# eth_part.net
KiCad netlist of a schematic drawn in Altium Designer
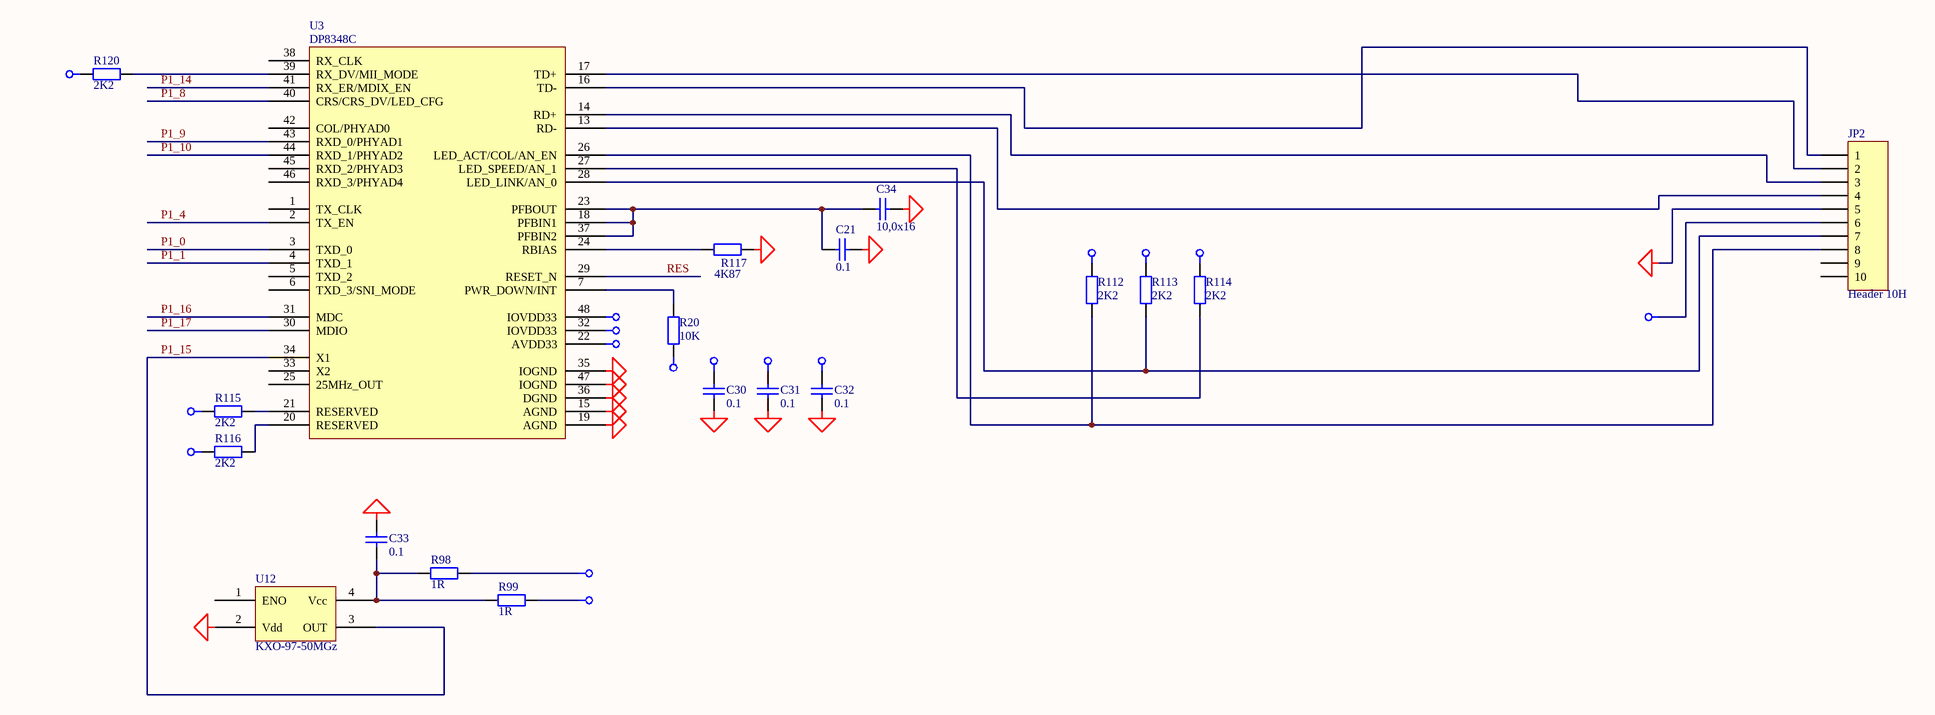
[diagram p0: eth_part.SchDoc]

(export (version "E")
  (design (tool "Eeschema 10.0.6"))
  (components
    (comp (ref "C21")
      (value "0.1")
      (footprint "C3216-1206")
      (description "Capacitor (Semiconductor SIM Model)")
      (fields (field (name "MANUFACTURER") "Generic Components") (field (name "PUBLISHER") "Altium Limited"))
      (libsource (lib "Miscellaneous Devices") (part "Cap Semi"))
    )
    (comp (ref "C30")
      (value "0.1")
      (footprint "_1206")
      (description "Capacitor (Semiconductor SIM Model)")
      (fields (field (name "MANUFACTURER") "Generic Components") (field (name "PUBLISHER") "Altium Limited"))
      (libsource (lib "Miscellaneous Devices") (part "Cap Semi"))
    )
    (comp (ref "C31")
      (value "0.1")
      (footprint "_1206")
      (description "Capacitor (Semiconductor SIM Model)")
      (fields (field (name "MANUFACTURER") "Generic Components") (field (name "PUBLISHER") "Altium Limited"))
      (libsource (lib "Miscellaneous Devices") (part "Cap Semi"))
    )
    (comp (ref "C32")
      (value "0.1")
      (footprint "_1206")
      (description "Capacitor (Semiconductor SIM Model)")
      (fields (field (name "MANUFACTURER") "Generic Components") (field (name "PUBLISHER") "Altium Limited"))
      (libsource (lib "Miscellaneous Devices") (part "Cap Semi"))
    )
    (comp (ref "C33")
      (value "0.1")
      (footprint "_1206")
      (description "Capacitor (Semiconductor SIM Model)")
      (fields (field (name "MANUFACTURER") "Generic Components") (field (name "PUBLISHER") "Altium Limited"))
      (libsource (lib "Miscellaneous Devices") (part "Cap Semi"))
    )
    (comp (ref "C34")
      (value "10,0x16")
      (footprint "C3216-1206")
      (description "Capacitor (Semiconductor SIM Model)")
      (fields (field (name "MANUFACTURER") "Generic Components") (field (name "PUBLISHER") "Altium Limited"))
      (libsource (lib "Miscellaneous Devices") (part "Cap Semi"))
    )
    (comp (ref "JP2")
      (value "Header 10H")
      (footprint "HDR2X5")
      (description "Header, 10-Pin, Right Angle")
      (fields (field (name "MANUFACTURER") "Generic Components") (field (name "PUBLISHER") "Altium Limited"))
      (libsource (lib "Miscellaneous Connectors") (part "Header 10H"))
    )
    (comp (ref "R20")
      (value "10K")
      (footprint "_1206")
      (description "Resistor")
      (fields (field (name "MANUFACTURER") "Generic Components") (field (name "PUBLISHER") "Altium Limited"))
      (libsource (lib "") (part "Res2_3"))
    )
    (comp (ref "R98")
      (value "1R")
      (footprint "_1206")
      (description "Resistor")
      (fields (field (name "MANUFACTURER") "Generic Components") (field (name "PUBLISHER") "Altium Limited"))
      (libsource (lib "") (part "Res2_1"))
    )
    (comp (ref "R99")
      (value "1R")
      (footprint "_1206")
      (description "Resistor")
      (fields (field (name "MANUFACTURER") "Generic Components") (field (name "PUBLISHER") "Altium Limited"))
      (libsource (lib "") (part "Res2_1"))
    )
    (comp (ref "R112")
      (value "2K2")
      (footprint "_1206")
      (description "Resistor")
      (fields (field (name "MANUFACTURER") "Generic Components") (field (name "PUBLISHER") "Altium Limited"))
      (libsource (lib "") (part "Res2_2"))
    )
    (comp (ref "R113")
      (value "2K2")
      (footprint "_1206")
      (description "Resistor")
      (fields (field (name "MANUFACTURER") "Generic Components") (field (name "PUBLISHER") "Altium Limited"))
      (libsource (lib "") (part "Res2_2"))
    )
    (comp (ref "R114")
      (value "2K2")
      (footprint "_1206")
      (description "Resistor")
      (fields (field (name "MANUFACTURER") "Generic Components") (field (name "PUBLISHER") "Altium Limited"))
      (libsource (lib "") (part "Res2_2"))
    )
    (comp (ref "R115")
      (value "2K2")
      (footprint "_1206")
      (description "Resistor")
      (fields (field (name "MANUFACTURER") "Generic Components") (field (name "PUBLISHER") "Altium Limited"))
      (libsource (lib "Miscellaneous Devices") (part "Res2"))
    )
    (comp (ref "R116")
      (value "2K2")
      (footprint "_1206")
      (description "Resistor")
      (fields (field (name "MANUFACTURER") "Generic Components") (field (name "PUBLISHER") "Altium Limited"))
      (libsource (lib "Miscellaneous Devices") (part "Res2"))
    )
    (comp (ref "R117")
      (value "4K87")
      (footprint "_1206")
      (description "Resistor")
      (fields (field (name "MANUFACTURER") "Generic Components") (field (name "PUBLISHER") "Altium Limited"))
      (libsource (lib "Miscellaneous Devices") (part "Res2"))
    )
    (comp (ref "R120")
      (value "2K2")
      (footprint "_1206")
      (description "Resistor")
      (fields (field (name "MANUFACTURER") "Generic Components") (field (name "PUBLISHER") "Altium Limited"))
      (libsource (lib "Miscellaneous Devices") (part "Res2"))
    )
    (comp (ref "U3") (value "DP8348C") (footprint "F-QFP7X7-G48/N") (libsource (lib "PAL") (part "DP8348C")))
    (comp (ref "U12") (value "KXO-97-50MGz") (footprint "KXO-97") (libsource (lib "PAL") (part "KXO-97")))
  )
  (nets
    (net (code "1") (name "+3v3") (class "Default")
      (node (ref "C30") (pin "1") (pinfunction "1_1") (pintype "passive"))
      (node (ref "C31") (pin "1") (pinfunction "1_1") (pintype "passive"))
      (node (ref "C32") (pin "1") (pinfunction "1_1") (pintype "passive"))
      (node (ref "JP2") (pin "6") (pinfunction "6_6") (pintype "passive"))
      (node (ref "R112") (pin "2") (pinfunction "2_2") (pintype "passive"))
      (node (ref "R113") (pin "2") (pinfunction "2_2") (pintype "passive"))
      (node (ref "R114") (pin "2") (pinfunction "2_2") (pintype "passive"))
      (node (ref "R115") (pin "2") (pinfunction "2_2") (pintype "passive"))
      (node (ref "R116") (pin "2") (pinfunction "2_2") (pintype "passive"))
      (node (ref "R120") (pin "2") (pinfunction "2_2") (pintype "passive"))
      (node (ref "R20") (pin "2") (pinfunction "2_2") (pintype "passive"))
      (node (ref "R99") (pin "2") (pinfunction "2_2") (pintype "passive"))
      (node (ref "U3") (pin "22") (pinfunction "AVDD33_22") (pintype "passive"))
      (node (ref "U3") (pin "32") (pinfunction "IOVDD33_32") (pintype "passive"))
      (node (ref "U3") (pin "48") (pinfunction "IOVDD33_48") (pintype "passive"))
    )
    (net (code "2") (name "+5v") (class "Default")
      (node (ref "R98") (pin "2") (pinfunction "2_2") (pintype "passive"))
    )
    (net (code "3") (name "/P1_0") (class "Default")
      (node (ref "U3") (pin "3") (pinfunction "TXD_0_3") (pintype "passive"))
    )
    (net (code "4") (name "/P1_1") (class "Default")
      (node (ref "U3") (pin "4") (pinfunction "TXD_1_4") (pintype "passive"))
    )
    (net (code "5") (name "/P1_4") (class "Default")
      (node (ref "U3") (pin "2") (pinfunction "TX_EN_2") (pintype "passive"))
    )
    (net (code "6") (name "/P1_8") (class "Default")
      (node (ref "U3") (pin "40") (pinfunction "CRS/CRS_DV/LED_CFG_40") (pintype "passive"))
    )
    (net (code "7") (name "/P1_9") (class "Default")
      (node (ref "U3") (pin "43") (pinfunction "RXD_0/PHYAD1_43") (pintype "passive"))
    )
    (net (code "8") (name "/P1_10") (class "Default")
      (node (ref "U3") (pin "44") (pinfunction "RXD_1/PHYAD2_44") (pintype "passive"))
    )
    (net (code "9") (name "/P1_14") (class "Default")
      (node (ref "U3") (pin "41") (pinfunction "RX_ER/MDIX_EN_41") (pintype "passive"))
    )
    (net (code "10") (name "/P1_15") (class "Default")
      (node (ref "U12") (pin "3") (pinfunction "OUT_3") (pintype "passive"))
      (node (ref "U3") (pin "34") (pinfunction "X1_34") (pintype "passive"))
    )
    (net (code "11") (name "/P1_16") (class "Default")
      (node (ref "U3") (pin "31") (pinfunction "MDC_31") (pintype "passive"))
    )
    (net (code "12") (name "/P1_17") (class "Default")
      (node (ref "U3") (pin "30") (pinfunction "MDIO_30") (pintype "passive"))
    )
    (net (code "13") (name "/RES") (class "Default")
      (node (ref "U3") (pin "29") (pinfunction "RESET_N_29") (pintype "passive"))
    )
    (net (code "14") (name "GND") (class "Default")
      (node (ref "C21") (pin "2") (pinfunction "2_2") (pintype "passive"))
      (node (ref "C30") (pin "2") (pinfunction "2_2") (pintype "passive"))
      (node (ref "C31") (pin "2") (pinfunction "2_2") (pintype "passive"))
      (node (ref "C32") (pin "2") (pinfunction "2_2") (pintype "passive"))
      (node (ref "C33") (pin "2") (pinfunction "2_2") (pintype "passive"))
      (node (ref "C34") (pin "2") (pinfunction "2_2") (pintype "passive"))
      (node (ref "JP2") (pin "5") (pinfunction "5_5") (pintype "passive"))
      (node (ref "R117") (pin "1") (pinfunction "1_1") (pintype "passive"))
      (node (ref "U12") (pin "2") (pinfunction "Vdd_2") (pintype "passive"))
      (node (ref "U3") (pin "15") (pinfunction "AGND_15") (pintype "passive"))
      (node (ref "U3") (pin "19") (pinfunction "AGND_19") (pintype "passive"))
      (node (ref "U3") (pin "35") (pinfunction "IOGND_35") (pintype "passive"))
      (node (ref "U3") (pin "36") (pinfunction "DGND_36") (pintype "passive"))
      (node (ref "U3") (pin "47") (pinfunction "IOGND_47") (pintype "passive"))
    )
    (net (code "15") (name "Net-(R115-Pad1)") (class "Default")
      (node (ref "R115") (pin "1") (pinfunction "1_1") (pintype "passive"))
      (node (ref "U3") (pin "21") (pinfunction "RESERVED_21") (pintype "passive"))
    )
    (net (code "16") (name "Net-(R116-Pad1)") (class "Default")
      (node (ref "R116") (pin "1") (pinfunction "1_1") (pintype "passive"))
      (node (ref "U3") (pin "20") (pinfunction "RESERVED_20") (pintype "passive"))
    )
    (net (code "17") (name "Net-(U3-LED_ACT{slash}COL{slash}AN_EN)") (class "Default")
      (node (ref "JP2") (pin "8") (pinfunction "8_8") (pintype "passive"))
      (node (ref "R112") (pin "1") (pinfunction "1_1") (pintype "passive"))
      (node (ref "U3") (pin "26") (pinfunction "LED_ACT/COL/AN_EN_26") (pintype "passive"))
    )
    (net (code "18") (name "Net-(U3-LED_LINK{slash}AN_0)") (class "Default")
      (node (ref "JP2") (pin "7") (pinfunction "7_7") (pintype "passive"))
      (node (ref "R113") (pin "1") (pinfunction "1_1") (pintype "passive"))
      (node (ref "U3") (pin "28") (pinfunction "LED_LINK/AN_0_28") (pintype "passive"))
    )
    (net (code "19") (name "Net-(U3-LED_SPEED{slash}AN_1)") (class "Default")
      (node (ref "R114") (pin "1") (pinfunction "1_1") (pintype "passive"))
      (node (ref "U3") (pin "27") (pinfunction "LED_SPEED/AN_1_27") (pintype "passive"))
    )
    (net (code "20") (name "Net-(U3-PFBIN1)") (class "Default")
      (node (ref "C21") (pin "1") (pinfunction "1_1") (pintype "passive"))
      (node (ref "C34") (pin "1") (pinfunction "1_1") (pintype "passive"))
      (node (ref "U3") (pin "18") (pinfunction "PFBIN1_18") (pintype "passive"))
      (node (ref "U3") (pin "23") (pinfunction "PFBOUT_23") (pintype "passive"))
      (node (ref "U3") (pin "37") (pinfunction "PFBIN2_37") (pintype "passive"))
    )
    (net (code "21") (name "Net-(U3-PWR_DOWN{slash}INT)") (class "Default")
      (node (ref "R20") (pin "1") (pinfunction "1_1") (pintype "passive"))
      (node (ref "U3") (pin "7") (pinfunction "PWR_DOWN/INT_7") (pintype "passive"))
    )
    (net (code "22") (name "Net-(U3-RBIAS)") (class "Default")
      (node (ref "R117") (pin "2") (pinfunction "2_2") (pintype "passive"))
      (node (ref "U3") (pin "24") (pinfunction "RBIAS_24") (pintype "passive"))
    )
    (net (code "23") (name "Net-(U3-RD+)") (class "Default")
      (node (ref "JP2") (pin "3") (pinfunction "3_3") (pintype "passive"))
      (node (ref "U3") (pin "14") (pinfunction "RD+_14") (pintype "passive"))
    )
    (net (code "24") (name "Net-(U3-RD-)") (class "Default")
      (node (ref "JP2") (pin "4") (pinfunction "4_4") (pintype "passive"))
      (node (ref "U3") (pin "13") (pinfunction "RD-_13") (pintype "passive"))
    )
    (net (code "25") (name "Net-(U3-RX_DV{slash}MII_MODE)") (class "Default")
      (node (ref "R120") (pin "1") (pinfunction "1_1") (pintype "passive"))
      (node (ref "U3") (pin "39") (pinfunction "RX_DV/MII_MODE_39") (pintype "passive"))
    )
    (net (code "26") (name "Net-(U3-TD+)") (class "Default")
      (node (ref "JP2") (pin "2") (pinfunction "2_2") (pintype "passive"))
      (node (ref "U3") (pin "17") (pinfunction "TD+_17") (pintype "passive"))
    )
    (net (code "27") (name "Net-(U3-TD-)") (class "Default")
      (node (ref "JP2") (pin "1") (pinfunction "1_1") (pintype "passive"))
      (node (ref "U3") (pin "16") (pinfunction "TD-_16") (pintype "passive"))
    )
    (net (code "28") (name "Net-(U12-Vcc)") (class "Default")
      (node (ref "C33") (pin "1") (pinfunction "1_1") (pintype "passive"))
      (node (ref "R98") (pin "1") (pinfunction "1_1") (pintype "passive"))
      (node (ref "R99") (pin "1") (pinfunction "1_1") (pintype "passive"))
      (node (ref "U12") (pin "4") (pinfunction "Vcc_4") (pintype "passive"))
    )
    (net (code "29") (name "unconnected-(JP2-Pad9)") (class "Default")
      (node (ref "JP2") (pin "9") (pinfunction "9_9") (pintype "passive"))
    )
    (net (code "30") (name "unconnected-(JP2-Pad10)") (class "Default")
      (node (ref "JP2") (pin "10") (pinfunction "10_10") (pintype "passive"))
    )
    (net (code "31") (name "unconnected-(U3-25MHz_OUT-Pad25)") (class "Default")
      (node (ref "U3") (pin "25") (pinfunction "25MHz_OUT_25") (pintype "passive"))
    )
    (net (code "32") (name "unconnected-(U3-COL{slash}PHYAD0-Pad42)") (class "Default")
      (node (ref "U3") (pin "42") (pinfunction "COL/PHYAD0_42") (pintype "passive"))
    )
    (net (code "33") (name "unconnected-(U3-RXD_2{slash}PHYAD3-Pad45)") (class "Default")
      (node (ref "U3") (pin "45") (pinfunction "RXD_2/PHYAD3_45") (pintype "passive"))
    )
    (net (code "34") (name "unconnected-(U3-RXD_3{slash}PHYAD4-Pad46)") (class "Default")
      (node (ref "U3") (pin "46") (pinfunction "RXD_3/PHYAD4_46") (pintype "passive"))
    )
    (net (code "35") (name "unconnected-(U3-RX_CLK-Pad38)") (class "Default")
      (node (ref "U3") (pin "38") (pinfunction "RX_CLK_38") (pintype "passive"))
    )
    (net (code "36") (name "unconnected-(U3-TXD_2-Pad5)") (class "Default")
      (node (ref "U3") (pin "5") (pinfunction "TXD_2_5") (pintype "passive"))
    )
    (net (code "37") (name "unconnected-(U3-TXD_3{slash}SNI_MODE-Pad6)") (class "Default")
      (node (ref "U3") (pin "6") (pinfunction "TXD_3/SNI_MODE_6") (pintype "passive"))
    )
    (net (code "38") (name "unconnected-(U3-TX_CLK-Pad1)") (class "Default")
      (node (ref "U3") (pin "1") (pinfunction "TX_CLK_1") (pintype "passive"))
    )
    (net (code "39") (name "unconnected-(U3-X2-Pad33)") (class "Default")
      (node (ref "U3") (pin "33") (pinfunction "X2_33") (pintype "passive"))
    )
    (net (code "40") (name "unconnected-(U12-ENO-Pad1)") (class "Default")
      (node (ref "U12") (pin "1") (pinfunction "ENO_1") (pintype "passive"))
    )
  )
)
